# LCD_SDcard.net
KiCad netlist of a schematic drawn in Altium Designer
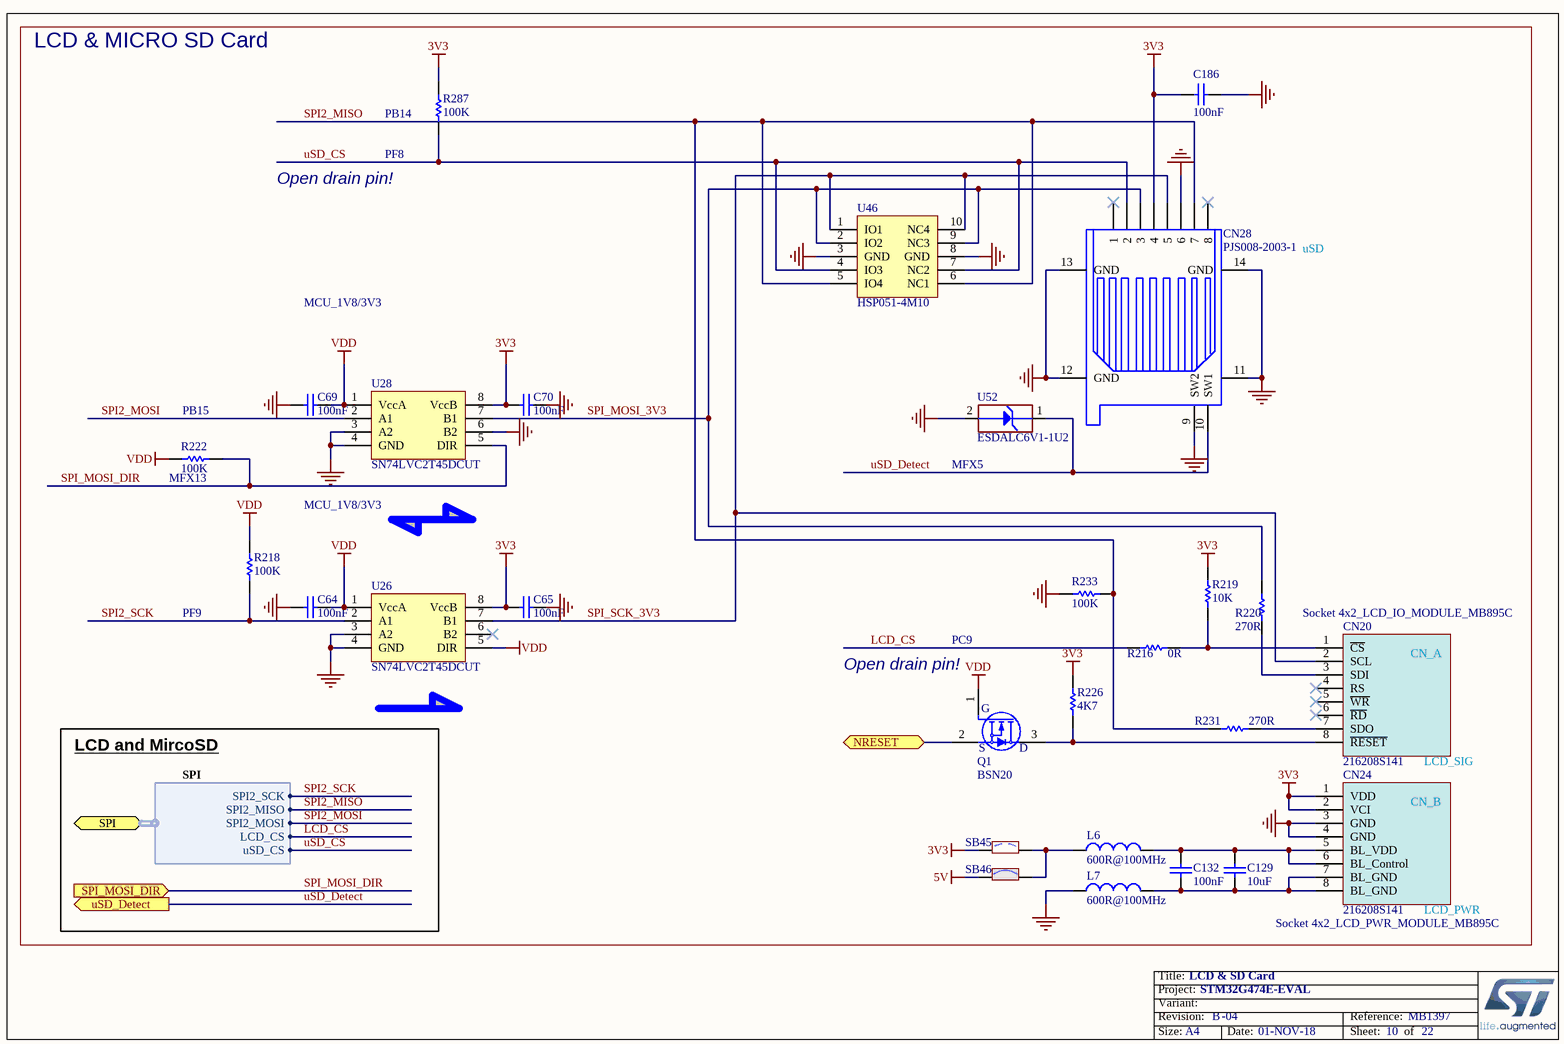
[diagram p0: LCD&SDcard.SchDoc]

(export (version "E")
  (design (tool "Eeschema 10.0.6"))
  (components
    (comp (ref "C64")
      (value "100nF")
      (footprint "C0603")
      (description "Capacitor, MLCC, 100nF, 16V, X7R, 10%, 0603, T=0,8mm")
      (fields
        (field (name "INTERNAL_PART_NUMBER") "MCD-00211")
        (field (name "MANUFACTURER_PART_NUMBER") "CC0603KRX7R7BB104")
        (field (name "PROVIDED_BY") "SUBCO")
      )
      (libsource (lib "MCD_PARTS_database") (part "Capacitor"))
    )
    (comp (ref "C65")
      (value "100nF")
      (footprint "C0603")
      (description "Capacitor, MLCC, 100nF, 16V, X7R, 10%, 0603, T=0,8mm")
      (fields
        (field (name "INTERNAL_PART_NUMBER") "MCD-00211")
        (field (name "MANUFACTURER_PART_NUMBER") "CC0603KRX7R7BB104")
        (field (name "PROVIDED_BY") "SUBCO")
      )
      (libsource (lib "MCD_PARTS_database") (part "Capacitor"))
    )
    (comp (ref "C69")
      (value "100nF")
      (footprint "C0603")
      (description "Capacitor, MLCC, 100nF, 16V, X7R, 10%, 0603, T=0,8mm")
      (fields
        (field (name "INTERNAL_PART_NUMBER") "MCD-00211")
        (field (name "MANUFACTURER_PART_NUMBER") "CC0603KRX7R7BB104")
        (field (name "PROVIDED_BY") "SUBCO")
      )
      (libsource (lib "MCD_PARTS_database") (part "Capacitor"))
    )
    (comp (ref "C70")
      (value "100nF")
      (footprint "C0603")
      (description "Capacitor, MLCC, 100nF, 16V, X7R, 10%, 0603, T=0,8mm")
      (fields
        (field (name "INTERNAL_PART_NUMBER") "MCD-00211")
        (field (name "MANUFACTURER_PART_NUMBER") "CC0603KRX7R7BB104")
        (field (name "PROVIDED_BY") "SUBCO")
      )
      (libsource (lib "MCD_PARTS_database") (part "Capacitor"))
    )
    (comp (ref "C129")
      (value "10uF")
      (footprint "C0805")
      (description "Capacitor, MLCC, 10uF, 25V, X5R, 10%, 0805, T=0,85mm")
      (fields
        (field (name "INTERNAL_PART_NUMBER") "MCD-00014")
        (field (name "MANUFACTURER_PART_NUMBER") "CC0805KRX5R8BB106")
        (field (name "PROVIDED_BY") "SUBCO")
      )
      (libsource (lib "MCD_PARTS_database") (part "Capacitor"))
    )
    (comp (ref "C132")
      (value "100nF")
      (footprint "C0402")
      (description "Capacitor, MLCC, 100nF, 16V, X7R, 10%, 0402, T=0.5mm")
      (fields
        (field (name "INTERNAL_PART_NUMBER") "MCD-00006")
        (field (name "MANUFACTURER_PART_NUMBER") "CC0402KRX7R7BB104")
        (field (name "PROVIDED_BY") "SUBCO")
      )
      (libsource (lib "MCD_PARTS_database") (part "Capacitor"))
    )
    (comp (ref "C186")
      (value "100nF")
      (footprint "C0402")
      (description "Capacitor, MLCC, 100nF, 16V, X7R, 10%, 0402, T=0.5mm")
      (fields
        (field (name "INTERNAL_PART_NUMBER") "MCD-00006")
        (field (name "MANUFACTURER_PART_NUMBER") "CC0402KRX7R7BB104")
        (field (name "PROVIDED_BY") "SUBCO")
      )
      (libsource (lib "MCD_PARTS_database") (part "Capacitor"))
    )
    (comp (ref "CN20")
      (value "Socket 4x2_LCD_IO_MODULE_MB895C")
      (footprint "CON_SOCKET-LCD_LYCN_216208S141")
      (description "Socket, 4x2, 2.54mm, VR, TH, Height 6.8mm, Double row")
      (fields
        (field (name "INTERNAL_PART_NUMBER") "MCD-01174")
        (field (name "ALTIUM_VALUE") "216208S141")
        (field (name "MANUFACTURER_PART_NUMBER") "216208S141")
        (field (name "PROVIDED_BY") "SUBCO")
      )
      (libsource (lib "MCD_PARTS_database") (part "Socket 4x2_LCD_IO_MODULE_MB895C"))
    )
    (comp (ref "CN24")
      (value "Socket 4x2_LCD_PWR_MODULE_MB895C")
      (footprint "CON_SOCKET-LCD_LYCN_216208S141")
      (description "socket, 4x2, 2.54mm, VR, TH, Height 6.8mm, Double row")
      (fields
        (field (name "INTERNAL_PART_NUMBER") "MCD-01195")
        (field (name "ALTIUM_VALUE") "216208S141")
        (field (name "MANUFACTURER_PART_NUMBER") "216208S141")
        (field (name "PROVIDED_BY") "SUBCO")
      )
      (libsource (lib "MCD_PARTS_database") (part "Socket 4x2_LCD_PWR_MODULE_MB895C"))
    )
    (comp (ref "CN28")
      (value "PJS008-2003-1")
      (footprint "CON_MICROSD_YAMAICHI_PJS008-2003-1")
      (description "MicroSD Card Conn, Reversed-Type, Mnt Push-Push, Positionning holes")
      (fields
        (field (name "INTERNAL_PART_NUMBER") "MCD-00023")
        (field (name "MANUFACTURER") "YAMAICHI")
        (field (name "PROVIDED_BY") "SUBCO")
      )
      (libsource (lib "MCD_PARTS_database") (part "microSD-PJS008-2003"))
    )
    (comp (ref "L6")
      (value "600R@100MHz")
      (footprint "L0603")
      (description "SMD Chip ferrite bead, 600R@100MHz +/-25%, 350mA, 500mohm DC, 0603, T=0.8mm")
      (fields
        (field (name "INTERNAL_PART_NUMBER") "MCD-00047")
        (field (name "MANUFACTURER_PART_NUMBER") "FCM1608KF-601T03")
        (field (name "PROVIDED_BY") "SUBCO")
      )
      (libsource (lib "MCD_PARTS_database") (part "BEAD"))
    )
    (comp (ref "L7")
      (value "600R@100MHz")
      (footprint "L0603")
      (description "SMD Chip ferrite bead, 600R@100MHz +/-25%, 350mA, 500mohm DC, 0603, T=0.8mm")
      (fields
        (field (name "INTERNAL_PART_NUMBER") "MCD-00047")
        (field (name "MANUFACTURER_PART_NUMBER") "FCM1608KF-601T03")
        (field (name "PROVIDED_BY") "SUBCO")
      )
      (libsource (lib "MCD_PARTS_database") (part "BEAD"))
    )
    (comp (ref "Q1")
      (value "BSN20")
      (footprint "MOS_SOT23")
      (description "N-channel enhancement mode field-effect transistor")
      (fields
        (field (name "INTERNAL_PART_NUMBER") "MCD-00151")
        (field (name "MANUFACTURER") "NXP")
        (field (name "PROVIDED_BY") "SUBCO")
      )
      (libsource (lib "MCD_PARTS_database") (part "BSN20"))
    )
    (comp (ref "R216")
      (value "0R")
      (footprint "R0603")
      (description "Resistor,0R,0603,5%,1/10W")
      (fields
        (field (name "INTERNAL_PART_NUMBER") "MCD-00056")
        (field (name "MANUFACTURER_PART_NUMBER") "RC0603JR-070RL")
        (field (name "PROVIDED_BY") "SUBCO")
      )
      (libsource (lib "MCD_PARTS_database") (part "Resistor"))
    )
    (comp (ref "R218")
      (value "100K")
      (footprint "R0603")
      (description "Resistor,100K,0603,1%,1/10W")
      (fields
        (field (name "INTERNAL_PART_NUMBER") "MCD-00223")
        (field (name "MANUFACTURER_PART_NUMBER") "RC0603FR-07100KL")
        (field (name "PROVIDED_BY") "SUBCO")
      )
      (libsource (lib "MCD_PARTS_database") (part "Resistor"))
    )
    (comp (ref "R219")
      (value "10K")
      (footprint "R0603")
      (description "Resistor,10K,0603,1%,1/10W")
      (fields
        (field (name "INTERNAL_PART_NUMBER") "MCD-00220")
        (field (name "MANUFACTURER_PART_NUMBER") "RC0603FR-0710KL")
        (field (name "PROVIDED_BY") "SUBCO")
      )
      (libsource (lib "MCD_PARTS_database") (part "Resistor"))
    )
    (comp (ref "R220")
      (value "270R")
      (footprint "R0603")
      (description "Resistor,270R,0603,1%,1/10W")
      (fields
        (field (name "INTERNAL_PART_NUMBER") "MCD-00442")
        (field (name "MANUFACTURER_PART_NUMBER") "RC0603FR-07270RL")
        (field (name "PROVIDED_BY") "SUBCO")
      )
      (libsource (lib "MCD_PARTS_database") (part "Resistor"))
    )
    (comp (ref "R222")
      (value "100K")
      (footprint "R0603")
      (description "Resistor,100K,0603,1%,1/10W")
      (fields
        (field (name "INTERNAL_PART_NUMBER") "MCD-00223")
        (field (name "MANUFACTURER_PART_NUMBER") "RC0603FR-07100KL")
        (field (name "PROVIDED_BY") "SUBCO")
      )
      (libsource (lib "MCD_PARTS_database") (part "Resistor"))
    )
    (comp (ref "R226")
      (value "4K7")
      (footprint "R0402")
      (description "Resistor,4K7,0402,1%,1/16W")
      (fields
        (field (name "INTERNAL_PART_NUMBER") "MCD-00065")
        (field (name "MANUFACTURER_PART_NUMBER") "RC0402FR-074K7L")
        (field (name "PROVIDED_BY") "SUBCO")
      )
      (libsource (lib "MCD_PARTS_database") (part "Resistor"))
    )
    (comp (ref "R231")
      (value "270R")
      (footprint "R0603")
      (description "Resistor,270R,0603,1%,1/10W")
      (fields
        (field (name "INTERNAL_PART_NUMBER") "MCD-00442")
        (field (name "MANUFACTURER_PART_NUMBER") "RC0603FR-07270RL")
        (field (name "PROVIDED_BY") "SUBCO")
      )
      (libsource (lib "MCD_PARTS_database") (part "Resistor"))
    )
    (comp (ref "R233")
      (value "100K")
      (footprint "R0603")
      (description "Resistor,100K,0603,1%,1/10W")
      (fields
        (field (name "INTERNAL_PART_NUMBER") "MCD-00223")
        (field (name "MANUFACTURER_PART_NUMBER") "RC0603FR-07100KL")
        (field (name "PROVIDED_BY") "SUBCO")
      )
      (libsource (lib "MCD_PARTS_database") (part "Resistor"))
    )
    (comp (ref "R287")
      (value "100K")
      (footprint "R0603")
      (description "Resistor,100K,0603,1%,1/10W")
      (fields
        (field (name "INTERNAL_PART_NUMBER") "MCD-00223")
        (field (name "MANUFACTURER_PART_NUMBER") "RC0603FR-07100KL")
        (field (name "PROVIDED_BY") "SUBCO")
      )
      (libsource (lib "MCD_PARTS_database") (part "Resistor"))
    )
    (comp (ref "SB45")
      (value "SB_OFF")
      (footprint "SOLDER-BRIDGE_R0603-0R")
      (description "Solder Bridge OFF")
      (fields
        (field (name "INTERNAL_PART_NUMBER") "MCD-00072")
        (field (name "MANUFACTURER_PART_NUMBER") "RC0603JR-070RL")
        (field (name "PROVIDED_BY") "SUBCO")
      )
      (libsource (lib "MCD_PARTS_database") (part "SB_OFF"))
    )
    (comp (ref "SB46")
      (value "SB_ON")
      (footprint "SOLDER-BRIDGE_R0603-0R")
      (description "Solder Bridge ON")
      (fields
        (field (name "INTERNAL_PART_NUMBER") "MCD-00071")
        (field (name "MANUFACTURER_PART_NUMBER") "RC0603JR-070RL")
        (field (name "PROVIDED_BY") "SUBCO")
      )
      (libsource (lib "MCD_PARTS_database") (part "SB_ON"))
    )
    (comp (ref "U26")
      (value "SN74LVC2T45DCUT")
      (footprint "ICC_VSSOP8_DCU_R-PDSO-G8_2X2P30_P050")
      (description "Dual bit dual supply bus transceiver")
      (fields
        (field (name "INTERNAL_PART_NUMBER") "MCD-00264")
        (field (name "MANUFACTURER") "TEXAS INSTRUMENTS")
        (field (name "PROVIDED_BY") "SUBCO")
      )
      (libsource (lib "MCD_PARTS_database") (part "SN74LVC2T45DCUT"))
    )
    (comp (ref "U28")
      (value "SN74LVC2T45DCUT")
      (footprint "ICC_VSSOP8_DCU_R-PDSO-G8_2X2P30_P050")
      (description "Dual bit dual supply bus transceiver")
      (fields
        (field (name "INTERNAL_PART_NUMBER") "MCD-00264")
        (field (name "MANUFACTURER") "TEXAS INSTRUMENTS")
        (field (name "PROVIDED_BY") "SUBCO")
      )
      (libsource (lib "MCD_PARTS_database") (part "SN74LVC2T45DCUT"))
    )
    (comp (ref "U46")
      (value "HSP051-4M10")
      (footprint "ESD_UQFN-10L_2P5X1_P050")
      (description "4-line ESD protection for high speed lines")
      (fields
        (field (name "MANUFACTURER") "STMICROELECTRONICS")
        (field (name "INTERNAL_PART_NUMBER") "MCD-00667")
        (field (name "PROVIDED_BY") "SUBCO with ST control")
      )
      (libsource (lib "MCD_PARTS_database") (part "HSP051-4M10"))
    )
    (comp (ref "U52")
      (value "ESDALC6V1-1U2")
      (footprint "ESD_ST0201")
      (description "ESD protection 6V1")
      (fields
        (field (name "INTERNAL_PART_NUMBER") "MCD-00170")
        (field (name "MANUFACTURER") "STMICROELECTRONICS")
        (field (name "PROVIDED_BY") "SUBCO with ST control")
      )
      (libsource (lib "MCD_PARTS_database") (part "ESD-TRANSIL"))
    )
  )
  (nets
    (net (code "2") (name "/LCD_CS") (class "Default")
      (node (ref "R216") (pin "1") (pinfunction "1_1") (pintype "passive"))
    )
    (net (code "3") (name "/NRESET") (class "Default")
      (node (ref "Q1") (pin "2") (pinfunction "S_2") (pintype "passive"))
    )
    (net (code "4") (name "/SPI2_MISO") (class "Default")
      (node (ref "CN28") (pin "7") (pinfunction "7_7") (pintype "passive"))
      (node (ref "R231") (pin "1") (pinfunction "1_1") (pintype "passive"))
      (node (ref "R233") (pin "1") (pinfunction "1_1") (pintype "passive"))
      (node (ref "U46") (pin "5") (pinfunction "IO4_5") (pintype "passive"))
      (node (ref "U46") (pin "6") (pinfunction "NC1_6") (pintype "passive"))
    )
    (net (code "5") (name "/SPI2_MOSI") (class "Default")
      (node (ref "U28") (pin "2") (pinfunction "A1_2") (pintype "passive"))
    )
    (net (code "6") (name "/SPI2_SCK") (class "Default")
      (node (ref "R218") (pin "1") (pinfunction "1_1") (pintype "passive"))
      (node (ref "U26") (pin "2") (pinfunction "A1_2") (pintype "passive"))
    )
    (net (code "7") (name "/SPI_MOSI_3V3") (class "Default")
      (node (ref "CN28") (pin "3") (pinfunction "3_3") (pintype "passive"))
      (node (ref "R220") (pin "1") (pinfunction "1_1") (pintype "passive"))
      (node (ref "U28") (pin "7") (pinfunction "B1_7") (pintype "passive"))
      (node (ref "U46") (pin "2") (pinfunction "IO2_2") (pintype "passive"))
      (node (ref "U46") (pin "9") (pinfunction "NC3_9") (pintype "passive"))
    )
    (net (code "8") (name "/SPI_MOSI_DIR") (class "Default")
      (node (ref "R222") (pin "1") (pinfunction "1_1") (pintype "passive"))
      (node (ref "U28") (pin "5") (pinfunction "DIR_5") (pintype "passive"))
    )
    (net (code "9") (name "/SPI_SCK_3V3") (class "Default")
      (node (ref "CN20") (pin "2") (pinfunction "SCL_2") (pintype "passive"))
      (node (ref "CN28") (pin "5") (pinfunction "5_5") (pintype "passive"))
      (node (ref "U26") (pin "7") (pinfunction "B1_7") (pintype "passive"))
      (node (ref "U46") (pin "1") (pinfunction "IO1_1") (pintype "passive"))
      (node (ref "U46") (pin "10") (pinfunction "NC4_10") (pintype "passive"))
    )
    (net (code "10") (name "/uSD_CS") (class "Default")
      (node (ref "CN28") (pin "2") (pinfunction "2_2") (pintype "passive"))
      (node (ref "R287") (pin "1") (pinfunction "1_1") (pintype "passive"))
      (node (ref "U46") (pin "4") (pinfunction "IO3_4") (pintype "passive"))
      (node (ref "U46") (pin "7") (pinfunction "NC2_7") (pintype "passive"))
    )
    (net (code "11") (name "/uSD_Detect") (class "Default")
      (node (ref "CN28") (pin "10") (pinfunction "SW1_10") (pintype "passive"))
      (node (ref "U52") (pin "1") (pinfunction "IO1_1") (pintype "passive"))
    )
    (net (code "13") (name "3V3") (class "Default")
      (node (ref "C186") (pin "1") (pinfunction "1_1") (pintype "passive"))
      (node (ref "C65") (pin "2") (pinfunction "2_2") (pintype "passive"))
      (node (ref "C70") (pin "2") (pinfunction "2_2") (pintype "passive"))
      (node (ref "CN24") (pin "1") (pinfunction "VDD_1") (pintype "passive"))
      (node (ref "CN24") (pin "2") (pinfunction "VCI_2") (pintype "passive"))
      (node (ref "CN28") (pin "4") (pinfunction "4_4") (pintype "passive"))
      (node (ref "R219") (pin "2") (pinfunction "2_2") (pintype "passive"))
      (node (ref "R226") (pin "1") (pinfunction "1_1") (pintype "passive"))
      (node (ref "R287") (pin "2") (pinfunction "2_2") (pintype "passive"))
      (node (ref "SB45") (pin "1") (pinfunction "1_1") (pintype "passive"))
      (node (ref "U26") (pin "8") (pinfunction "VccB_8") (pintype "power_in"))
      (node (ref "U28") (pin "8") (pinfunction "VccB_8") (pintype "power_in"))
    )
    (net (code "14") (name "5V") (class "Default")
      (node (ref "SB46") (pin "1") (pinfunction "1_1") (pintype "passive"))
    )
    (net (code "15") (name "GND") (class "Default")
      (node (ref "C186") (pin "2") (pinfunction "2_2") (pintype "passive"))
      (node (ref "C64") (pin "2") (pinfunction "2_2") (pintype "passive"))
      (node (ref "C65") (pin "1") (pinfunction "1_1") (pintype "passive"))
      (node (ref "C69") (pin "2") (pinfunction "2_2") (pintype "passive"))
      (node (ref "C70") (pin "1") (pinfunction "1_1") (pintype "passive"))
      (node (ref "CN24") (pin "3") (pinfunction "GND_3") (pintype "passive"))
      (node (ref "CN24") (pin "4") (pinfunction "GND_4") (pintype "passive"))
      (node (ref "CN28") (pin "11") (pinfunction "GND_11") (pintype "passive"))
      (node (ref "CN28") (pin "12") (pinfunction "GND_12") (pintype "passive"))
      (node (ref "CN28") (pin "13") (pinfunction "GND_13") (pintype "passive"))
      (node (ref "CN28") (pin "14") (pinfunction "GND_14") (pintype "passive"))
      (node (ref "CN28") (pin "6") (pinfunction "6_6") (pintype "passive"))
      (node (ref "CN28") (pin "9") (pinfunction "SW2_9") (pintype "passive"))
      (node (ref "L7") (pin "1") (pinfunction "1_1") (pintype "passive"))
      (node (ref "R233") (pin "2") (pinfunction "2_2") (pintype "passive"))
      (node (ref "U26") (pin "3") (pinfunction "A2_3") (pintype "passive"))
      (node (ref "U26") (pin "4") (pinfunction "GND_4") (pintype "power_in"))
      (node (ref "U28") (pin "3") (pinfunction "A2_3") (pintype "passive"))
      (node (ref "U28") (pin "4") (pinfunction "GND_4") (pintype "power_in"))
      (node (ref "U28") (pin "6") (pinfunction "B2_6") (pintype "passive"))
      (node (ref "U46") (pin "3") (pinfunction "GND_3") (pintype "passive"))
      (node (ref "U46") (pin "8") (pinfunction "GND_8") (pintype "passive"))
      (node (ref "U52") (pin "2") (pinfunction "GND_2") (pintype "passive"))
    )
    (net (code "16") (name "Net-(C129-Pad2)") (class "Default")
      (node (ref "C129") (pin "2") (pinfunction "2_2") (pintype "passive"))
      (node (ref "C132") (pin "1") (pinfunction "1_1") (pintype "passive"))
      (node (ref "CN24") (pin "7") (pinfunction "BL_GND_7") (pintype "passive"))
      (node (ref "CN24") (pin "8") (pinfunction "BL_GND_8") (pintype "passive"))
      (node (ref "L7") (pin "2") (pinfunction "2_2") (pintype "passive"))
    )
    (net (code "17") (name "Net-(CN20-SDI)") (class "Default")
      (node (ref "CN20") (pin "3") (pinfunction "SDI_3") (pintype "passive"))
      (node (ref "R220") (pin "2") (pinfunction "2_2") (pintype "passive"))
    )
    (net (code "18") (name "Net-(CN20-SDO)") (class "Default")
      (node (ref "CN20") (pin "7") (pinfunction "SDO_7") (pintype "passive"))
      (node (ref "R231") (pin "2") (pinfunction "2_2") (pintype "passive"))
    )
    (net (code "19") (name "Net-(CN20-~{CS})") (class "Default")
      (node (ref "CN20") (pin "1") (pinfunction "~{CS}_1") (pintype "passive"))
      (node (ref "R216") (pin "2") (pinfunction "2_2") (pintype "passive"))
      (node (ref "R219") (pin "1") (pinfunction "1_1") (pintype "passive"))
    )
    (net (code "20") (name "Net-(CN20-~{RESET})") (class "Default")
      (node (ref "CN20") (pin "8") (pinfunction "~{RESET}_8") (pintype "passive"))
      (node (ref "Q1") (pin "3") (pinfunction "D_3") (pintype "passive"))
      (node (ref "R226") (pin "2") (pinfunction "2_2") (pintype "passive"))
    )
    (net (code "21") (name "Net-(CN24-BL_Control)") (class "Default")
      (node (ref "C129") (pin "1") (pinfunction "1_1") (pintype "passive"))
      (node (ref "C132") (pin "2") (pinfunction "2_2") (pintype "passive"))
      (node (ref "CN24") (pin "5") (pinfunction "BL_VDD_5") (pintype "passive"))
      (node (ref "CN24") (pin "6") (pinfunction "BL_Control_6") (pintype "passive"))
      (node (ref "L6") (pin "2") (pinfunction "2_2") (pintype "passive"))
    )
    (net (code "22") (name "Net-(L6-Pad1)") (class "Default")
      (node (ref "L6") (pin "1") (pinfunction "1_1") (pintype "passive"))
      (node (ref "SB45") (pin "2") (pinfunction "2_2") (pintype "passive"))
      (node (ref "SB46") (pin "2") (pinfunction "2_2") (pintype "passive"))
    )
    (net (code "23") (name "VDD") (class "Default")
      (node (ref "C64") (pin "1") (pinfunction "1_1") (pintype "passive"))
      (node (ref "C69") (pin "1") (pinfunction "1_1") (pintype "passive"))
      (node (ref "Q1") (pin "1") (pinfunction "G_1") (pintype "passive"))
      (node (ref "R218") (pin "2") (pinfunction "2_2") (pintype "passive"))
      (node (ref "R222") (pin "2") (pinfunction "2_2") (pintype "passive"))
      (node (ref "U26") (pin "1") (pinfunction "VccA_1") (pintype "power_in"))
      (node (ref "U26") (pin "5") (pinfunction "DIR_5") (pintype "passive"))
      (node (ref "U28") (pin "1") (pinfunction "VccA_1") (pintype "power_in"))
    )
    (net (code "24") (name "unconnected-(CN20-RS-Pad4)") (class "Default")
      (node (ref "CN20") (pin "4") (pinfunction "RS_4") (pintype "passive+no_connect"))
    )
    (net (code "25") (name "unconnected-(CN20-~{RD}-Pad6)") (class "Default")
      (node (ref "CN20") (pin "6") (pinfunction "~{RD}_6") (pintype "passive+no_connect"))
    )
    (net (code "26") (name "unconnected-(CN20-~{WR}-Pad5)") (class "Default")
      (node (ref "CN20") (pin "5") (pinfunction "~{WR}_5") (pintype "passive+no_connect"))
    )
    (net (code "27") (name "unconnected-(CN28-Pad1)") (class "Default")
      (node (ref "CN28") (pin "1") (pinfunction "1_1") (pintype "passive+no_connect"))
    )
    (net (code "28") (name "unconnected-(CN28-Pad8)") (class "Default")
      (node (ref "CN28") (pin "8") (pinfunction "8_8") (pintype "passive+no_connect"))
    )
    (net (code "29") (name "unconnected-(U26-B2-Pad6)") (class "Default")
      (node (ref "U26") (pin "6") (pinfunction "B2_6") (pintype "passive+no_connect"))
    )
  )
)
